# Gums.net
KiCad netlist of a schematic drawn in EAGLE
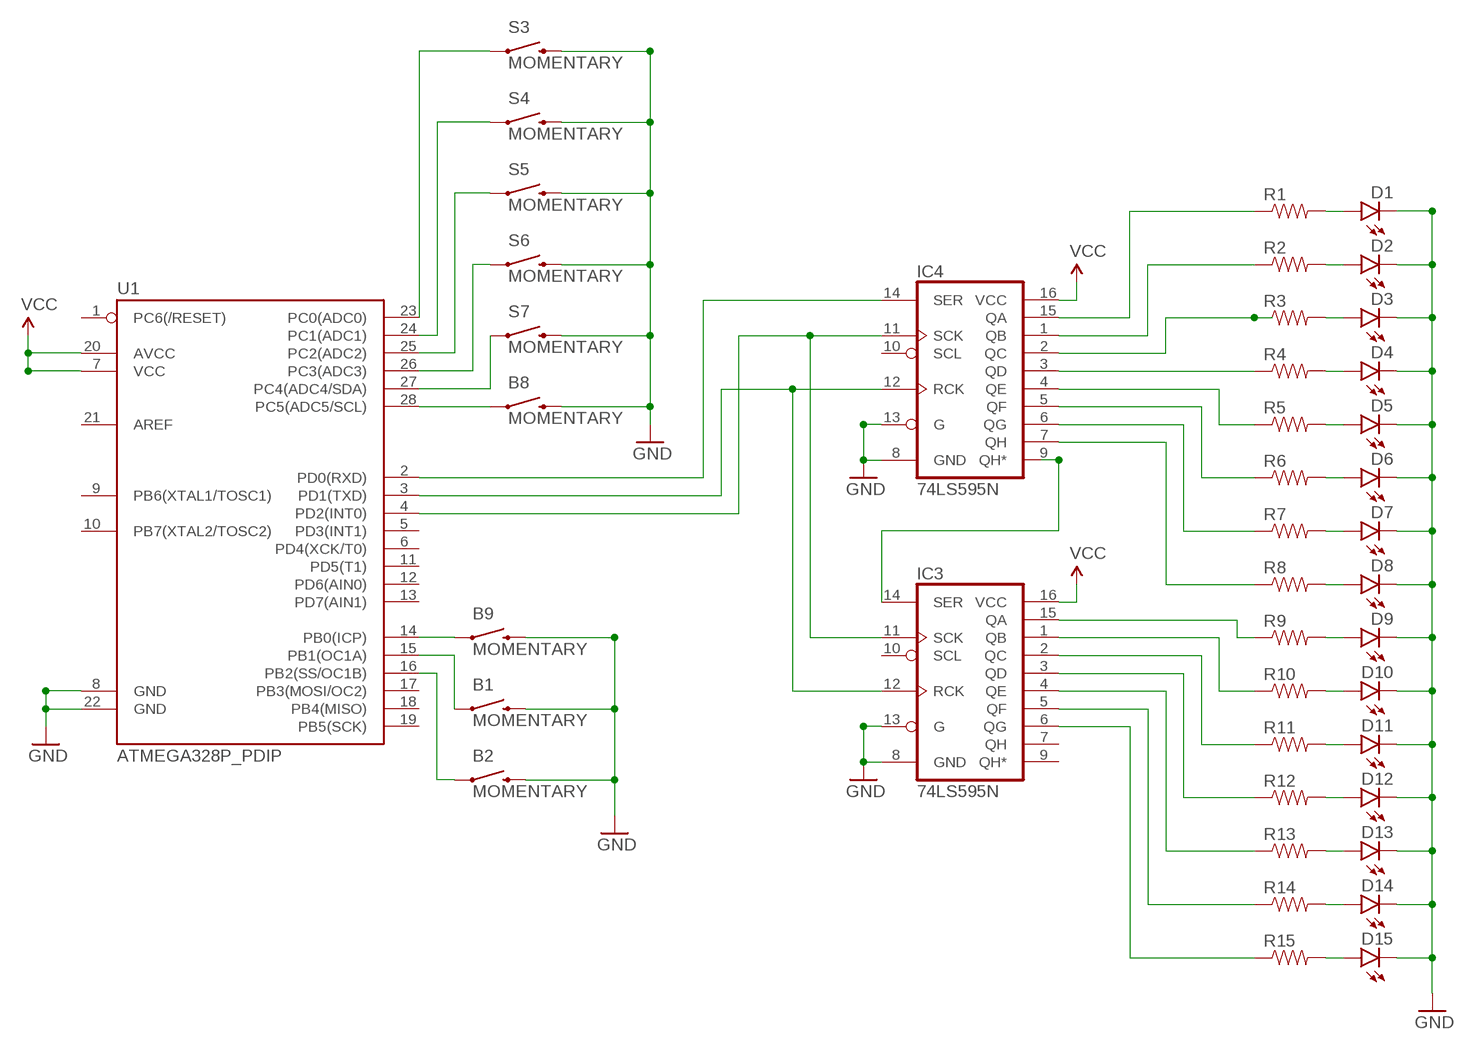
[diagram p0: schematic, sheet 1]

(export (version "E")
  (design (tool "Eeschema 10.0.6"))
  (components
    (comp (ref "B1")
      (value "MOMENTARY")
      (footprint "eagle-import:TACTILE-SMD-12MM")
      (libsource (lib "eagle-import") (part "SWITCH-MOMENTARY-2SMD-12MM"))
    )
    (comp (ref "B2")
      (value "MOMENTARY")
      (footprint "eagle-import:TACTILE-SMD-12MM")
      (libsource (lib "eagle-import") (part "SWITCH-MOMENTARY-2SMD-12MM"))
    )
    (comp (ref "B8")
      (value "MOMENTARY")
      (footprint "eagle-import:TACTILE-SMD-12MM")
      (libsource (lib "eagle-import") (part "SWITCH-MOMENTARY-2SMD-12MM"))
    )
    (comp (ref "B9")
      (value "MOMENTARY")
      (footprint "eagle-import:TACTILE-SMD-12MM")
      (libsource (lib "eagle-import") (part "SWITCH-MOMENTARY-2SMD-12MM"))
    )
    (comp (ref "D1")
      (value "LED5MM")
      (footprint "eagle-import:LED5MM")
      (libsource (lib "eagle-import") (part "LED5MM"))
    )
    (comp (ref "D2")
      (value "LED5MM")
      (footprint "eagle-import:LED5MM")
      (libsource (lib "eagle-import") (part "LED5MM"))
    )
    (comp (ref "D3")
      (value "LED5MM")
      (footprint "eagle-import:LED5MM")
      (libsource (lib "eagle-import") (part "LED5MM"))
    )
    (comp (ref "D4")
      (value "LED5MM")
      (footprint "eagle-import:LED5MM")
      (libsource (lib "eagle-import") (part "LED5MM"))
    )
    (comp (ref "D5")
      (value "LED5MM")
      (footprint "eagle-import:LED5MM")
      (libsource (lib "eagle-import") (part "LED5MM"))
    )
    (comp (ref "D6")
      (value "LED5MM")
      (footprint "eagle-import:LED5MM")
      (libsource (lib "eagle-import") (part "LED5MM"))
    )
    (comp (ref "D7")
      (value "LED5MM")
      (footprint "eagle-import:LED5MM")
      (libsource (lib "eagle-import") (part "LED5MM"))
    )
    (comp (ref "D8")
      (value "LED5MM")
      (footprint "eagle-import:LED5MM")
      (libsource (lib "eagle-import") (part "LED5MM"))
    )
    (comp (ref "D9")
      (value "LED5MM")
      (footprint "eagle-import:LED5MM")
      (libsource (lib "eagle-import") (part "LED5MM"))
    )
    (comp (ref "D10")
      (value "LED5MM")
      (footprint "eagle-import:LED5MM")
      (libsource (lib "eagle-import") (part "LED5MM"))
    )
    (comp (ref "D11")
      (value "LED5MM")
      (footprint "eagle-import:LED5MM")
      (libsource (lib "eagle-import") (part "LED5MM"))
    )
    (comp (ref "D12")
      (value "LED5MM")
      (footprint "eagle-import:LED5MM")
      (libsource (lib "eagle-import") (part "LED5MM"))
    )
    (comp (ref "D13")
      (value "LED5MM")
      (footprint "eagle-import:LED5MM")
      (libsource (lib "eagle-import") (part "LED5MM"))
    )
    (comp (ref "D14")
      (value "LED5MM")
      (footprint "eagle-import:LED5MM")
      (libsource (lib "eagle-import") (part "LED5MM"))
    )
    (comp (ref "D15")
      (value "LED5MM")
      (footprint "eagle-import:LED5MM")
      (libsource (lib "eagle-import") (part "LED5MM"))
    )
    (comp (ref "IC3")
      (value "74LS595N")
      (footprint "eagle-import:DIL16")
      (libsource (lib "eagle-import") (part "74595NLS"))
    )
    (comp (ref "IC4")
      (value "74LS595N")
      (footprint "eagle-import:DIL16")
      (libsource (lib "eagle-import") (part "74595NLS"))
    )
    (comp (ref "R1")
      (value "RESISTORPTH-1/4W")
      (footprint "eagle-import:AXIAL-0.4")
      (libsource (lib "eagle-import") (part "RESISTORPTH-1/4W"))
    )
    (comp (ref "R2")
      (value "RESISTORPTH-1/4W")
      (footprint "eagle-import:AXIAL-0.4")
      (libsource (lib "eagle-import") (part "RESISTORPTH-1/4W"))
    )
    (comp (ref "R3")
      (value "RESISTORPTH-1/4W")
      (footprint "eagle-import:AXIAL-0.4")
      (libsource (lib "eagle-import") (part "RESISTORPTH-1/4W"))
    )
    (comp (ref "R4")
      (value "RESISTORPTH-1/4W")
      (footprint "eagle-import:AXIAL-0.4")
      (libsource (lib "eagle-import") (part "RESISTORPTH-1/4W"))
    )
    (comp (ref "R5")
      (value "RESISTORPTH-1/4W")
      (footprint "eagle-import:AXIAL-0.4")
      (libsource (lib "eagle-import") (part "RESISTORPTH-1/4W"))
    )
    (comp (ref "R6")
      (value "RESISTORPTH-1/4W")
      (footprint "eagle-import:AXIAL-0.4")
      (libsource (lib "eagle-import") (part "RESISTORPTH-1/4W"))
    )
    (comp (ref "R7")
      (value "RESISTORPTH-1/4W")
      (footprint "eagle-import:AXIAL-0.4")
      (libsource (lib "eagle-import") (part "RESISTORPTH-1/4W"))
    )
    (comp (ref "R8")
      (value "RESISTORPTH-1/4W")
      (footprint "eagle-import:AXIAL-0.4")
      (libsource (lib "eagle-import") (part "RESISTORPTH-1/4W"))
    )
    (comp (ref "R9")
      (value "RESISTORPTH-1/4W")
      (footprint "eagle-import:AXIAL-0.4")
      (libsource (lib "eagle-import") (part "RESISTORPTH-1/4W"))
    )
    (comp (ref "R10")
      (value "RESISTORPTH-1/4W")
      (footprint "eagle-import:AXIAL-0.4")
      (libsource (lib "eagle-import") (part "RESISTORPTH-1/4W"))
    )
    (comp (ref "R11")
      (value "RESISTORPTH-1/4W")
      (footprint "eagle-import:AXIAL-0.4")
      (libsource (lib "eagle-import") (part "RESISTORPTH-1/4W"))
    )
    (comp (ref "R12")
      (value "RESISTORPTH-1/4W")
      (footprint "eagle-import:AXIAL-0.4")
      (libsource (lib "eagle-import") (part "RESISTORPTH-1/4W"))
    )
    (comp (ref "R13")
      (value "RESISTORPTH-1/4W")
      (footprint "eagle-import:AXIAL-0.4")
      (libsource (lib "eagle-import") (part "RESISTORPTH-1/4W"))
    )
    (comp (ref "R14")
      (value "RESISTORPTH-1/4W")
      (footprint "eagle-import:AXIAL-0.4")
      (libsource (lib "eagle-import") (part "RESISTORPTH-1/4W"))
    )
    (comp (ref "R15")
      (value "RESISTORPTH-1/4W")
      (footprint "eagle-import:AXIAL-0.4")
      (libsource (lib "eagle-import") (part "RESISTORPTH-1/4W"))
    )
    (comp (ref "S3")
      (value "MOMENTARY")
      (footprint "eagle-import:TACTILE-SMD-12MM")
      (libsource (lib "eagle-import") (part "SWITCH-MOMENTARY-2SMD-12MM"))
    )
    (comp (ref "S4")
      (value "MOMENTARY")
      (footprint "eagle-import:TACTILE-SMD-12MM")
      (libsource (lib "eagle-import") (part "SWITCH-MOMENTARY-2SMD-12MM"))
    )
    (comp (ref "S5")
      (value "MOMENTARY")
      (footprint "eagle-import:TACTILE-SMD-12MM")
      (libsource (lib "eagle-import") (part "SWITCH-MOMENTARY-2SMD-12MM"))
    )
    (comp (ref "S6")
      (value "MOMENTARY")
      (footprint "eagle-import:TACTILE-SMD-12MM")
      (libsource (lib "eagle-import") (part "SWITCH-MOMENTARY-2SMD-12MM"))
    )
    (comp (ref "S7")
      (value "MOMENTARY")
      (footprint "eagle-import:TACTILE-SMD-12MM")
      (libsource (lib "eagle-import") (part "SWITCH-MOMENTARY-2SMD-12MM"))
    )
    (comp (ref "U1")
      (value "ATMEGA328P_PDIP")
      (footprint "eagle-import:DIL28-3")
      (libsource (lib "eagle-import") (part "ATMEGA328P_PDIP"))
    )
  )
  (nets
    (net (code "1") (name "GND") (class "Default")
      (node (ref "B1") (pin "3") (pinfunction "2_3") (pintype "passive"))
      (node (ref "B2") (pin "3") (pinfunction "2_3") (pintype "passive"))
      (node (ref "B8") (pin "3") (pinfunction "2_3") (pintype "passive"))
      (node (ref "B9") (pin "3") (pinfunction "2_3") (pintype "passive"))
      (node (ref "D1") (pin "K") (pinfunction "C_K") (pintype "passive"))
      (node (ref "D10") (pin "K") (pinfunction "C_K") (pintype "passive"))
      (node (ref "D11") (pin "K") (pinfunction "C_K") (pintype "passive"))
      (node (ref "D12") (pin "K") (pinfunction "C_K") (pintype "passive"))
      (node (ref "D13") (pin "K") (pinfunction "C_K") (pintype "passive"))
      (node (ref "D14") (pin "K") (pinfunction "C_K") (pintype "passive"))
      (node (ref "D15") (pin "K") (pinfunction "C_K") (pintype "passive"))
      (node (ref "D2") (pin "K") (pinfunction "C_K") (pintype "passive"))
      (node (ref "D3") (pin "K") (pinfunction "C_K") (pintype "passive"))
      (node (ref "D4") (pin "K") (pinfunction "C_K") (pintype "passive"))
      (node (ref "D5") (pin "K") (pinfunction "C_K") (pintype "passive"))
      (node (ref "D6") (pin "K") (pinfunction "C_K") (pintype "passive"))
      (node (ref "D7") (pin "K") (pinfunction "C_K") (pintype "passive"))
      (node (ref "D8") (pin "K") (pinfunction "C_K") (pintype "passive"))
      (node (ref "D9") (pin "K") (pinfunction "C_K") (pintype "passive"))
      (node (ref "IC3") (pin "13") (pinfunction "G_13") (pintype "input"))
      (node (ref "IC3") (pin "8") (pinfunction "GND_8") (pintype "power_in"))
      (node (ref "IC4") (pin "13") (pinfunction "G_13") (pintype "input"))
      (node (ref "IC4") (pin "8") (pinfunction "GND_8") (pintype "power_in"))
      (node (ref "S3") (pin "3") (pinfunction "2_3") (pintype "passive"))
      (node (ref "S4") (pin "3") (pinfunction "2_3") (pintype "passive"))
      (node (ref "S5") (pin "3") (pinfunction "2_3") (pintype "passive"))
      (node (ref "S6") (pin "3") (pinfunction "2_3") (pintype "passive"))
      (node (ref "S7") (pin "3") (pinfunction "2_3") (pintype "passive"))
      (node (ref "U1") (pin "22") (pinfunction "GND_22") (pintype "bidirectional"))
      (node (ref "U1") (pin "8") (pinfunction "GND_8") (pintype "bidirectional"))
    )
    (net (code "2") (name "Net-(IC3-QA)") (class "Default")
      (node (ref "IC3") (pin "15") (pinfunction "QA_15") (pintype "tri_state"))
      (node (ref "R9") (pin "P$1") (pinfunction "1_P$1") (pintype "passive"))
    )
    (net (code "3") (name "Net-(IC3-QB)") (class "Default")
      (node (ref "IC3") (pin "1") (pinfunction "QB_1") (pintype "tri_state"))
      (node (ref "R10") (pin "P$1") (pinfunction "1_P$1") (pintype "passive"))
    )
    (net (code "4") (name "Net-(IC3-QC)") (class "Default")
      (node (ref "IC3") (pin "2") (pinfunction "QC_2") (pintype "tri_state"))
      (node (ref "R11") (pin "P$1") (pinfunction "1_P$1") (pintype "passive"))
    )
    (net (code "5") (name "Net-(IC3-QD)") (class "Default")
      (node (ref "IC3") (pin "3") (pinfunction "QD_3") (pintype "tri_state"))
      (node (ref "R12") (pin "P$1") (pinfunction "1_P$1") (pintype "passive"))
    )
    (net (code "6") (name "Net-(IC3-QE)") (class "Default")
      (node (ref "IC3") (pin "4") (pinfunction "QE_4") (pintype "tri_state"))
      (node (ref "R13") (pin "P$1") (pinfunction "1_P$1") (pintype "passive"))
    )
    (net (code "7") (name "Net-(IC3-QF)") (class "Default")
      (node (ref "IC3") (pin "5") (pinfunction "QF_5") (pintype "tri_state"))
      (node (ref "R14") (pin "P$1") (pinfunction "1_P$1") (pintype "passive"))
    )
    (net (code "8") (name "Net-(IC3-QG)") (class "Default")
      (node (ref "IC3") (pin "6") (pinfunction "QG_6") (pintype "tri_state"))
      (node (ref "R15") (pin "P$1") (pinfunction "1_P$1") (pintype "passive"))
    )
    (net (code "9") (name "Net-(IC3-RCK)") (class "Default")
      (node (ref "IC3") (pin "12") (pinfunction "RCK_12") (pintype "input"))
      (node (ref "IC4") (pin "12") (pinfunction "RCK_12") (pintype "input"))
      (node (ref "U1") (pin "3") (pinfunction "PD1(TXD)_3") (pintype "bidirectional"))
    )
    (net (code "10") (name "Net-(IC3-SCK)") (class "Default")
      (node (ref "IC3") (pin "11") (pinfunction "SCK_11") (pintype "input"))
      (node (ref "IC4") (pin "11") (pinfunction "SCK_11") (pintype "input"))
      (node (ref "U1") (pin "4") (pinfunction "PD2(INT0)_4") (pintype "bidirectional"))
    )
    (net (code "11") (name "Net-(IC3-SER)") (class "Default")
      (node (ref "IC3") (pin "14") (pinfunction "SER_14") (pintype "input"))
      (node (ref "IC4") (pin "9") (pinfunction "QH*_9") (pintype "tri_state"))
    )
    (net (code "12") (name "Net-(IC4-QA)") (class "Default")
      (node (ref "IC4") (pin "15") (pinfunction "QA_15") (pintype "tri_state"))
      (node (ref "R1") (pin "P$1") (pinfunction "1_P$1") (pintype "passive"))
    )
    (net (code "13") (name "Net-(IC4-QB)") (class "Default")
      (node (ref "IC4") (pin "1") (pinfunction "QB_1") (pintype "tri_state"))
      (node (ref "R2") (pin "P$1") (pinfunction "1_P$1") (pintype "passive"))
    )
    (net (code "14") (name "Net-(IC4-QC)") (class "Default")
      (node (ref "IC4") (pin "2") (pinfunction "QC_2") (pintype "tri_state"))
      (node (ref "R3") (pin "P$1") (pinfunction "1_P$1") (pintype "passive"))
    )
    (net (code "15") (name "Net-(IC4-QD)") (class "Default")
      (node (ref "IC4") (pin "3") (pinfunction "QD_3") (pintype "tri_state"))
      (node (ref "R4") (pin "P$1") (pinfunction "1_P$1") (pintype "passive"))
    )
    (net (code "16") (name "Net-(IC4-QE)") (class "Default")
      (node (ref "IC4") (pin "4") (pinfunction "QE_4") (pintype "tri_state"))
      (node (ref "R5") (pin "P$1") (pinfunction "1_P$1") (pintype "passive"))
    )
    (net (code "17") (name "Net-(IC4-QF)") (class "Default")
      (node (ref "IC4") (pin "5") (pinfunction "QF_5") (pintype "tri_state"))
      (node (ref "R6") (pin "P$1") (pinfunction "1_P$1") (pintype "passive"))
    )
    (net (code "18") (name "Net-(IC4-QG)") (class "Default")
      (node (ref "IC4") (pin "6") (pinfunction "QG_6") (pintype "tri_state"))
      (node (ref "R7") (pin "P$1") (pinfunction "1_P$1") (pintype "passive"))
    )
    (net (code "19") (name "Net-(IC4-QH)") (class "Default")
      (node (ref "IC4") (pin "7") (pinfunction "QH_7") (pintype "tri_state"))
      (node (ref "R8") (pin "P$1") (pinfunction "1_P$1") (pintype "passive"))
    )
    (net (code "20") (name "Net-(IC4-SER)") (class "Default")
      (node (ref "IC4") (pin "14") (pinfunction "SER_14") (pintype "input"))
      (node (ref "U1") (pin "2") (pinfunction "PD0(RXD)_2") (pintype "bidirectional"))
    )
    (net (code "21") (name "Net-(R1-2)") (class "Default")
      (node (ref "D1") (pin "A") (pinfunction "A_A") (pintype "passive"))
      (node (ref "R1") (pin "P$2") (pinfunction "2_P$2") (pintype "passive"))
    )
    (net (code "22") (name "Net-(R2-2)") (class "Default")
      (node (ref "D2") (pin "A") (pinfunction "A_A") (pintype "passive"))
      (node (ref "R2") (pin "P$2") (pinfunction "2_P$2") (pintype "passive"))
    )
    (net (code "23") (name "Net-(R3-2)") (class "Default")
      (node (ref "D3") (pin "A") (pinfunction "A_A") (pintype "passive"))
      (node (ref "R3") (pin "P$2") (pinfunction "2_P$2") (pintype "passive"))
    )
    (net (code "24") (name "Net-(R4-2)") (class "Default")
      (node (ref "D4") (pin "A") (pinfunction "A_A") (pintype "passive"))
      (node (ref "R4") (pin "P$2") (pinfunction "2_P$2") (pintype "passive"))
    )
    (net (code "25") (name "Net-(R5-2)") (class "Default")
      (node (ref "D5") (pin "A") (pinfunction "A_A") (pintype "passive"))
      (node (ref "R5") (pin "P$2") (pinfunction "2_P$2") (pintype "passive"))
    )
    (net (code "26") (name "Net-(R6-2)") (class "Default")
      (node (ref "D6") (pin "A") (pinfunction "A_A") (pintype "passive"))
      (node (ref "R6") (pin "P$2") (pinfunction "2_P$2") (pintype "passive"))
    )
    (net (code "27") (name "Net-(R7-2)") (class "Default")
      (node (ref "D7") (pin "A") (pinfunction "A_A") (pintype "passive"))
      (node (ref "R7") (pin "P$2") (pinfunction "2_P$2") (pintype "passive"))
    )
    (net (code "28") (name "Net-(R8-2)") (class "Default")
      (node (ref "D8") (pin "A") (pinfunction "A_A") (pintype "passive"))
      (node (ref "R8") (pin "P$2") (pinfunction "2_P$2") (pintype "passive"))
    )
    (net (code "29") (name "Net-(R9-2)") (class "Default")
      (node (ref "D9") (pin "A") (pinfunction "A_A") (pintype "passive"))
      (node (ref "R9") (pin "P$2") (pinfunction "2_P$2") (pintype "passive"))
    )
    (net (code "30") (name "Net-(R10-2)") (class "Default")
      (node (ref "D10") (pin "A") (pinfunction "A_A") (pintype "passive"))
      (node (ref "R10") (pin "P$2") (pinfunction "2_P$2") (pintype "passive"))
    )
    (net (code "31") (name "Net-(R11-2)") (class "Default")
      (node (ref "D11") (pin "A") (pinfunction "A_A") (pintype "passive"))
      (node (ref "R11") (pin "P$2") (pinfunction "2_P$2") (pintype "passive"))
    )
    (net (code "32") (name "Net-(R12-2)") (class "Default")
      (node (ref "D12") (pin "A") (pinfunction "A_A") (pintype "passive"))
      (node (ref "R12") (pin "P$2") (pinfunction "2_P$2") (pintype "passive"))
    )
    (net (code "33") (name "Net-(R13-2)") (class "Default")
      (node (ref "D13") (pin "A") (pinfunction "A_A") (pintype "passive"))
      (node (ref "R13") (pin "P$2") (pinfunction "2_P$2") (pintype "passive"))
    )
    (net (code "34") (name "Net-(R14-2)") (class "Default")
      (node (ref "D14") (pin "A") (pinfunction "A_A") (pintype "passive"))
      (node (ref "R14") (pin "P$2") (pinfunction "2_P$2") (pintype "passive"))
    )
    (net (code "35") (name "Net-(R15-2)") (class "Default")
      (node (ref "D15") (pin "A") (pinfunction "A_A") (pintype "passive"))
      (node (ref "R15") (pin "P$2") (pinfunction "2_P$2") (pintype "passive"))
    )
    (net (code "36") (name "Net-(U1-PB0(ICP))") (class "Default")
      (node (ref "B9") (pin "1") (pinfunction "1_1") (pintype "passive"))
      (node (ref "U1") (pin "14") (pinfunction "PB0(ICP)_14") (pintype "bidirectional"))
    )
    (net (code "37") (name "Net-(U1-PB1(OC1A))") (class "Default")
      (node (ref "B1") (pin "1") (pinfunction "1_1") (pintype "passive"))
      (node (ref "U1") (pin "15") (pinfunction "PB1(OC1A)_15") (pintype "bidirectional"))
    )
    (net (code "38") (name "Net-(U1-PB2(SS{slash}OC1B))") (class "Default")
      (node (ref "B2") (pin "1") (pinfunction "1_1") (pintype "passive"))
      (node (ref "U1") (pin "16") (pinfunction "PB2(SS/OC1B)_16") (pintype "bidirectional"))
    )
    (net (code "39") (name "Net-(U1-PC0(ADC0))") (class "Default")
      (node (ref "S3") (pin "1") (pinfunction "1_1") (pintype "passive"))
      (node (ref "U1") (pin "23") (pinfunction "PC0(ADC0)_23") (pintype "bidirectional"))
    )
    (net (code "40") (name "Net-(U1-PC1(ADC1))") (class "Default")
      (node (ref "S4") (pin "1") (pinfunction "1_1") (pintype "passive"))
      (node (ref "U1") (pin "24") (pinfunction "PC1(ADC1)_24") (pintype "bidirectional"))
    )
    (net (code "41") (name "Net-(U1-PC2(ADC2))") (class "Default")
      (node (ref "S5") (pin "1") (pinfunction "1_1") (pintype "passive"))
      (node (ref "U1") (pin "25") (pinfunction "PC2(ADC2)_25") (pintype "bidirectional"))
    )
    (net (code "42") (name "Net-(U1-PC3(ADC3))") (class "Default")
      (node (ref "S6") (pin "1") (pinfunction "1_1") (pintype "passive"))
      (node (ref "U1") (pin "26") (pinfunction "PC3(ADC3)_26") (pintype "bidirectional"))
    )
    (net (code "43") (name "Net-(U1-PC4(ADC4{slash}SDA))") (class "Default")
      (node (ref "S7") (pin "1") (pinfunction "1_1") (pintype "passive"))
      (node (ref "U1") (pin "27") (pinfunction "PC4(ADC4/SDA)_27") (pintype "bidirectional"))
    )
    (net (code "44") (name "Net-(U1-PC5(ADC5{slash}SCL))") (class "Default")
      (node (ref "B8") (pin "1") (pinfunction "1_1") (pintype "passive"))
      (node (ref "U1") (pin "28") (pinfunction "PC5(ADC5/SCL)_28") (pintype "bidirectional"))
    )
    (net (code "45") (name "VCC") (class "Default")
      (node (ref "IC3") (pin "16") (pinfunction "VCC_16") (pintype "power_in"))
      (node (ref "IC4") (pin "16") (pinfunction "VCC_16") (pintype "power_in"))
      (node (ref "U1") (pin "20") (pinfunction "AVCC_20") (pintype "bidirectional"))
      (node (ref "U1") (pin "7") (pinfunction "VCC_7") (pintype "bidirectional"))
    )
    (net (code "46") (name "unconnected-(IC3-QH*-Pad9)") (class "Default")
      (node (ref "IC3") (pin "9") (pinfunction "QH*_9") (pintype "tri_state"))
    )
    (net (code "47") (name "unconnected-(IC3-QH-Pad7)") (class "Default")
      (node (ref "IC3") (pin "7") (pinfunction "QH_7") (pintype "tri_state"))
    )
    (net (code "48") (name "unconnected-(IC3-SCL-Pad10)") (class "Default")
      (node (ref "IC3") (pin "10") (pinfunction "SCL_10") (pintype "input"))
    )
    (net (code "49") (name "unconnected-(IC4-SCL-Pad10)") (class "Default")
      (node (ref "IC4") (pin "10") (pinfunction "SCL_10") (pintype "input"))
    )
    (net (code "50") (name "unconnected-(U1-AREF-Pad21)") (class "Default")
      (node (ref "U1") (pin "21") (pinfunction "AREF_21") (pintype "bidirectional"))
    )
    (net (code "51") (name "unconnected-(U1-PB3(MOSI{slash}OC2)-Pad17)") (class "Default")
      (node (ref "U1") (pin "17") (pinfunction "PB3(MOSI/OC2)_17") (pintype "bidirectional"))
    )
    (net (code "52") (name "unconnected-(U1-PB4(MISO)-Pad18)") (class "Default")
      (node (ref "U1") (pin "18") (pinfunction "PB4(MISO)_18") (pintype "bidirectional"))
    )
    (net (code "53") (name "unconnected-(U1-PB5(SCK)-Pad19)") (class "Default")
      (node (ref "U1") (pin "19") (pinfunction "PB5(SCK)_19") (pintype "bidirectional"))
    )
    (net (code "54") (name "unconnected-(U1-PB6(XTAL1{slash}TOSC1)-Pad9)") (class "Default")
      (node (ref "U1") (pin "9") (pinfunction "PB6(XTAL1/TOSC1)_9") (pintype "bidirectional"))
    )
    (net (code "55") (name "unconnected-(U1-PB7(XTAL2{slash}TOSC2)-Pad10)") (class "Default")
      (node (ref "U1") (pin "10") (pinfunction "PB7(XTAL2/TOSC2)_10") (pintype "bidirectional"))
    )
    (net (code "56") (name "unconnected-(U1-PC6({slash}RESET)-Pad1)") (class "Default")
      (node (ref "U1") (pin "1") (pinfunction "PC6(/RESET)_1") (pintype "bidirectional"))
    )
    (net (code "57") (name "unconnected-(U1-PD3(INT1)-Pad5)") (class "Default")
      (node (ref "U1") (pin "5") (pinfunction "PD3(INT1)_5") (pintype "bidirectional"))
    )
    (net (code "58") (name "unconnected-(U1-PD4(XCK{slash}T0)-Pad6)") (class "Default")
      (node (ref "U1") (pin "6") (pinfunction "PD4(XCK/T0)_6") (pintype "bidirectional"))
    )
    (net (code "59") (name "unconnected-(U1-PD5(T1)-Pad11)") (class "Default")
      (node (ref "U1") (pin "11") (pinfunction "PD5(T1)_11") (pintype "bidirectional"))
    )
    (net (code "60") (name "unconnected-(U1-PD6(AIN0)-Pad12)") (class "Default")
      (node (ref "U1") (pin "12") (pinfunction "PD6(AIN0)_12") (pintype "bidirectional"))
    )
    (net (code "61") (name "unconnected-(U1-PD7(AIN1)-Pad13)") (class "Default")
      (node (ref "U1") (pin "13") (pinfunction "PD7(AIN1)_13") (pintype "bidirectional"))
    )
  )
)
